# control.net
KiCad netlist of a schematic drawn in EAGLE
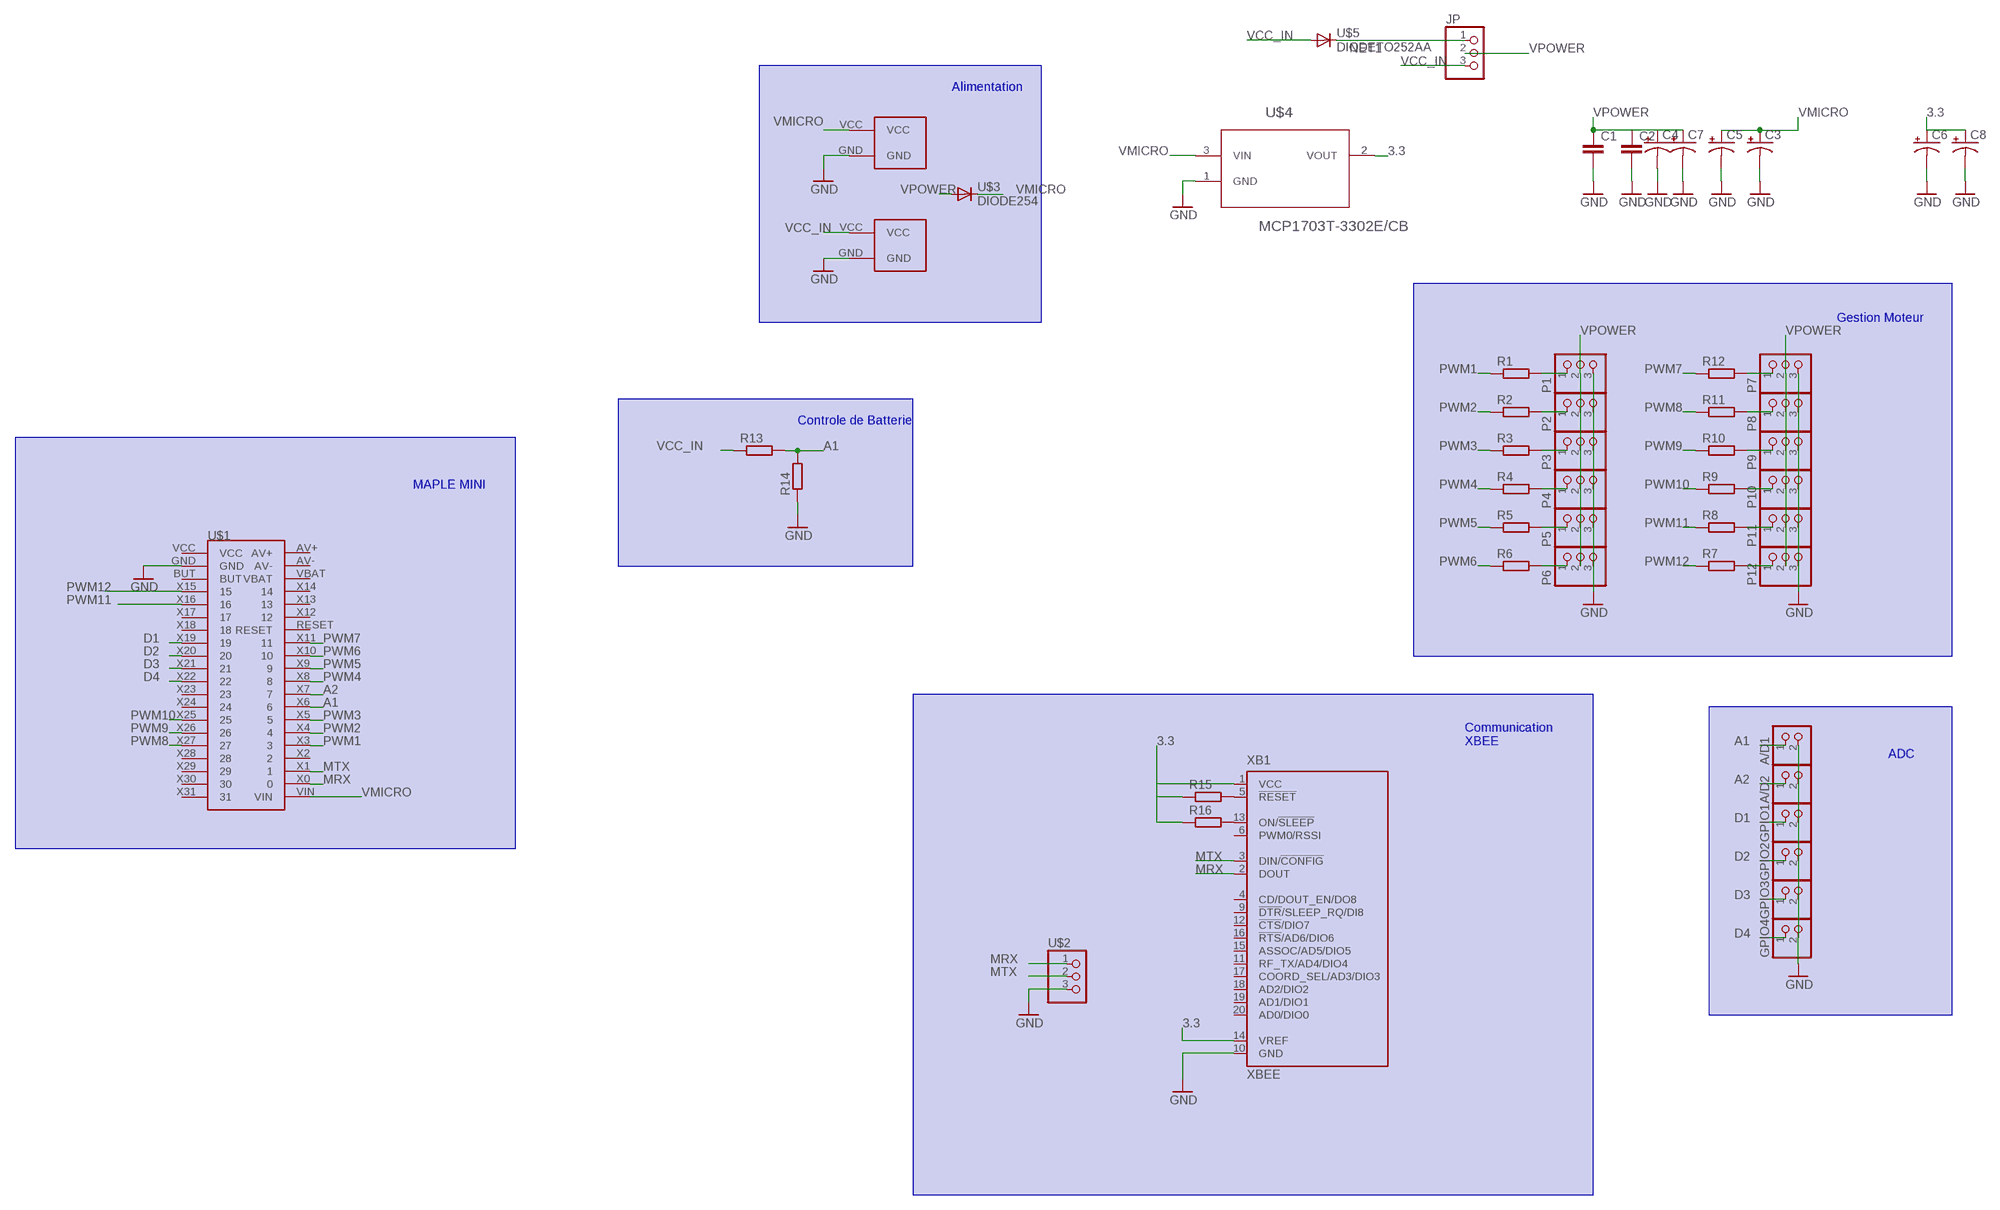
[diagram p0: schematic, sheet 1]

(export (version "E")
  (design (tool "Eeschema 10.0.6"))
  (components
    (comp (ref "A/D1")
      (value "CONNEC_1X02")
      (footprint "eagle-import:CONNEC_1X02")
      (libsource (lib "eagle-import") (part "CONNEC_1X02"))
    )
    (comp (ref "A/D2")
      (value "CONNEC_1X02")
      (footprint "eagle-import:CONNEC_1X02")
      (libsource (lib "eagle-import") (part "CONNEC_1X02"))
    )
    (comp (ref "C1")
      (value "C-EU075-032X103")
      (footprint "eagle-import:C075-032X103")
      (libsource (lib "eagle-import") (part "C-EU075-032X103"))
    )
    (comp (ref "C2")
      (value "C-EU075-032X103")
      (footprint "eagle-import:C075-032X103")
      (libsource (lib "eagle-import") (part "C-EU075-032X103"))
    )
    (comp (ref "C3")
      (value "CAP_POLPTH2")
      (footprint "eagle-import:CPOL-RADIAL-10UF-25V")
      (libsource (lib "eagle-import") (part "CAP_POLPTH2"))
    )
    (comp (ref "C4")
      (value "CAP_POLPTH2")
      (footprint "eagle-import:CPOL-RADIAL-10UF-25V")
      (libsource (lib "eagle-import") (part "CAP_POLPTH2"))
    )
    (comp (ref "C5")
      (value "CAP_POLPTH2")
      (footprint "eagle-import:CPOL-RADIAL-10UF-25V")
      (libsource (lib "eagle-import") (part "CAP_POLPTH2"))
    )
    (comp (ref "C6")
      (value "CAP_POLPTH2")
      (footprint "eagle-import:CPOL-RADIAL-10UF-25V")
      (libsource (lib "eagle-import") (part "CAP_POLPTH2"))
    )
    (comp (ref "C7")
      (value "CAP_POLPTH2")
      (footprint "eagle-import:CPOL-RADIAL-10UF-25V")
      (libsource (lib "eagle-import") (part "CAP_POLPTH2"))
    )
    (comp (ref "C8")
      (value "CAP_POLPTH2")
      (footprint "eagle-import:CPOL-RADIAL-10UF-25V")
      (libsource (lib "eagle-import") (part "CAP_POLPTH2"))
    )
    (comp (ref "GPIO1")
      (value "CONNEC_1X02")
      (footprint "eagle-import:CONNEC_1X02")
      (libsource (lib "eagle-import") (part "CONNEC_1X02"))
    )
    (comp (ref "GPIO2")
      (value "CONNEC_1X02")
      (footprint "eagle-import:CONNEC_1X02")
      (libsource (lib "eagle-import") (part "CONNEC_1X02"))
    )
    (comp (ref "GPIO3")
      (value "CONNEC_1X02")
      (footprint "eagle-import:CONNEC_1X02")
      (libsource (lib "eagle-import") (part "CONNEC_1X02"))
    )
    (comp (ref "GPIO4")
      (value "CONNEC_1X02")
      (footprint "eagle-import:CONNEC_1X02")
      (libsource (lib "eagle-import") (part "CONNEC_1X02"))
    )
    (comp (ref "JP")
      (value "CONNEC_1X03")
      (footprint "eagle-import:CONNEC_1X03")
      (libsource (lib "eagle-import") (part "CONNEC_1X03"))
    )
    (comp (ref "P1")
      (value "CONNEC_1X03")
      (footprint "eagle-import:CONNEC_1X03")
      (libsource (lib "eagle-import") (part "rhoban_CONNEC_1X03"))
    )
    (comp (ref "P2")
      (value "CONNEC_1X03")
      (footprint "eagle-import:CONNEC_1X03")
      (libsource (lib "eagle-import") (part "rhoban_CONNEC_1X03"))
    )
    (comp (ref "P3")
      (value "CONNEC_1X03")
      (footprint "eagle-import:CONNEC_1X03")
      (libsource (lib "eagle-import") (part "rhoban_CONNEC_1X03"))
    )
    (comp (ref "P4")
      (value "CONNEC_1X03")
      (footprint "eagle-import:CONNEC_1X03")
      (libsource (lib "eagle-import") (part "rhoban_CONNEC_1X03"))
    )
    (comp (ref "P5")
      (value "CONNEC_1X03")
      (footprint "eagle-import:CONNEC_1X03")
      (libsource (lib "eagle-import") (part "rhoban_CONNEC_1X03"))
    )
    (comp (ref "P6")
      (value "CONNEC_1X03")
      (footprint "eagle-import:CONNEC_1X03")
      (libsource (lib "eagle-import") (part "rhoban_CONNEC_1X03"))
    )
    (comp (ref "P7")
      (value "CONNEC_1X03")
      (footprint "eagle-import:CONNEC_1X03")
      (libsource (lib "eagle-import") (part "rhoban_CONNEC_1X03"))
    )
    (comp (ref "P8")
      (value "CONNEC_1X03")
      (footprint "eagle-import:CONNEC_1X03")
      (libsource (lib "eagle-import") (part "rhoban_CONNEC_1X03"))
    )
    (comp (ref "P9")
      (value "CONNEC_1X03")
      (footprint "eagle-import:CONNEC_1X03")
      (libsource (lib "eagle-import") (part "rhoban_CONNEC_1X03"))
    )
    (comp (ref "P10")
      (value "CONNEC_1X03")
      (footprint "eagle-import:CONNEC_1X03")
      (libsource (lib "eagle-import") (part "rhoban_CONNEC_1X03"))
    )
    (comp (ref "P11")
      (value "CONNEC_1X03")
      (footprint "eagle-import:CONNEC_1X03")
      (libsource (lib "eagle-import") (part "rhoban_CONNEC_1X03"))
    )
    (comp (ref "P12")
      (value "CONNEC_1X03")
      (footprint "eagle-import:CONNEC_1X03")
      (libsource (lib "eagle-import") (part "rhoban_CONNEC_1X03"))
    )
    (comp (ref "R1")
      (value "RESISTANCE-R0805")
      (footprint "eagle-import:R0805")
      (libsource (lib "eagle-import") (part "RESISTANCE-R0805"))
    )
    (comp (ref "R2")
      (value "RESISTANCE-R0805")
      (footprint "eagle-import:R0805")
      (libsource (lib "eagle-import") (part "RESISTANCE-R0805"))
    )
    (comp (ref "R3")
      (value "RESISTANCE-R0805")
      (footprint "eagle-import:R0805")
      (libsource (lib "eagle-import") (part "RESISTANCE-R0805"))
    )
    (comp (ref "R4")
      (value "RESISTANCE-R0805")
      (footprint "eagle-import:R0805")
      (libsource (lib "eagle-import") (part "RESISTANCE-R0805"))
    )
    (comp (ref "R5")
      (value "RESISTANCE-R0805")
      (footprint "eagle-import:R0805")
      (libsource (lib "eagle-import") (part "RESISTANCE-R0805"))
    )
    (comp (ref "R6")
      (value "RESISTANCE-R0805")
      (footprint "eagle-import:R0805")
      (libsource (lib "eagle-import") (part "RESISTANCE-R0805"))
    )
    (comp (ref "R7")
      (value "RESISTANCE-R0805")
      (footprint "eagle-import:R0805")
      (libsource (lib "eagle-import") (part "RESISTANCE-R0805"))
    )
    (comp (ref "R8")
      (value "RESISTANCE-R0805")
      (footprint "eagle-import:R0805")
      (libsource (lib "eagle-import") (part "RESISTANCE-R0805"))
    )
    (comp (ref "R9")
      (value "RESISTANCE-R0805")
      (footprint "eagle-import:R0805")
      (libsource (lib "eagle-import") (part "RESISTANCE-R0805"))
    )
    (comp (ref "R10")
      (value "RESISTANCE-R0805")
      (footprint "eagle-import:R0805")
      (libsource (lib "eagle-import") (part "RESISTANCE-R0805"))
    )
    (comp (ref "R11")
      (value "RESISTANCE-R0805")
      (footprint "eagle-import:R0805")
      (libsource (lib "eagle-import") (part "RESISTANCE-R0805"))
    )
    (comp (ref "R12")
      (value "RESISTANCE-R0805")
      (footprint "eagle-import:R0805")
      (libsource (lib "eagle-import") (part "RESISTANCE-R0805"))
    )
    (comp (ref "R13")
      (value "R-EU_R0805")
      (footprint "eagle-import:R0805")
      (libsource (lib "eagle-import") (part "R-EU_R0805"))
    )
    (comp (ref "R14")
      (value "R-EU_R0805")
      (footprint "eagle-import:R0805")
      (libsource (lib "eagle-import") (part "R-EU_R0805"))
    )
    (comp (ref "R15")
      (value "R-EU_R0805")
      (footprint "eagle-import:R0805")
      (libsource (lib "eagle-import") (part "R-EU_R0805"))
    )
    (comp (ref "R16")
      (value "R-EU_R0805")
      (footprint "eagle-import:R0805")
      (libsource (lib "eagle-import") (part "R-EU_R0805"))
    )
    (comp (ref "U$1")
      (value "MAPLE_MINI")
      (footprint "eagle-import:CONNEC_2X20")
      (libsource (lib "eagle-import") (part "MAPLE_MINI"))
    )
    (comp (ref "U$2")
      (value "CONNEC_1X03")
      (footprint "eagle-import:CONNEC_1X03")
      (libsource (lib "eagle-import") (part "CONNEC_1X03"))
    )
    (comp (ref "U$3")
      (value "DIODE254")
      (footprint "eagle-import:DIODE_254")
      (libsource (lib "eagle-import") (part "RobotCampus_DIODE254"))
    )
    (comp (ref "U$4")
      (value "MCP1703T-3302E/CB")
      (footprint "eagle-import:SOT95P300X145-3N")
      (libsource (lib "eagle-import") (part "MCP1703T-3302E/CB"))
    )
    (comp (ref "U$5")
      (value "DIODETO252AA")
      (footprint "eagle-import:TO-252AA")
      (libsource (lib "eagle-import") (part "DIODETO252AA"))
    )
    (comp (ref "U$10")
      (value "JST_2")
      (footprint "eagle-import:JST_2")
      (libsource (lib "eagle-import") (part "JST_2"))
    )
    (comp (ref "U$11")
      (value "JST_2")
      (footprint "eagle-import:JST_2")
      (libsource (lib "eagle-import") (part "JST_2"))
    )
    (comp (ref "XB1")
      (value "XBEE")
      (footprint "eagle-import:XBEE")
      (fields (field (name "MPN") "XBP24-Z7UIT-004"))
      (libsource (lib "eagle-import") (part "XBEE"))
    )
  )
  (nets
    (net (code "1") (name "/3.3") (class "Default")
      (node (ref "C6") (pin "1") (pinfunction "+_1") (pintype "passive"))
      (node (ref "C8") (pin "1") (pinfunction "+_1") (pintype "passive"))
      (node (ref "R15") (pin "1") (pinfunction "1_1") (pintype "passive"))
      (node (ref "R16") (pin "1") (pinfunction "1_1") (pintype "passive"))
      (node (ref "U$4") (pin "2") (pinfunction "VOUT_2") (pintype "output"))
      (node (ref "XB1") (pin "1") (pinfunction "VCC_1") (pintype "power_in"))
      (node (ref "XB1") (pin "14") (pinfunction "VREF_14") (pintype "input"))
    )
    (net (code "2") (name "/A1") (class "Default")
      (node (ref "A/D1") (pin "1") (pinfunction "1_1") (pintype "passive"))
      (node (ref "R13") (pin "2") (pinfunction "2_2") (pintype "passive"))
      (node (ref "R14") (pin "2") (pinfunction "2_2") (pintype "passive"))
      (node (ref "U$1") (pin "X6") (pinfunction "6_X6") (pintype "bidirectional"))
    )
    (net (code "3") (name "/A2") (class "Default")
      (node (ref "A/D2") (pin "1") (pinfunction "1_1") (pintype "passive"))
      (node (ref "U$1") (pin "X7") (pinfunction "7_X7") (pintype "bidirectional"))
    )
    (net (code "4") (name "/D1") (class "Default")
      (node (ref "GPIO1") (pin "1") (pinfunction "1_1") (pintype "passive"))
      (node (ref "U$1") (pin "X19") (pinfunction "19_X19") (pintype "bidirectional"))
    )
    (net (code "5") (name "/D2") (class "Default")
      (node (ref "GPIO2") (pin "1") (pinfunction "1_1") (pintype "passive"))
      (node (ref "U$1") (pin "X20") (pinfunction "20_X20") (pintype "bidirectional"))
    )
    (net (code "6") (name "/D3") (class "Default")
      (node (ref "GPIO3") (pin "1") (pinfunction "1_1") (pintype "passive"))
      (node (ref "U$1") (pin "X21") (pinfunction "21_X21") (pintype "bidirectional"))
    )
    (net (code "7") (name "/D4") (class "Default")
      (node (ref "GPIO4") (pin "1") (pinfunction "1_1") (pintype "passive"))
      (node (ref "U$1") (pin "X22") (pinfunction "22_X22") (pintype "bidirectional"))
    )
    (net (code "8") (name "/MRX") (class "Default")
      (node (ref "U$1") (pin "X0") (pinfunction "0_X0") (pintype "bidirectional"))
      (node (ref "U$2") (pin "1") (pinfunction "1_1") (pintype "passive"))
      (node (ref "XB1") (pin "2") (pinfunction "DOUT_2") (pintype "output"))
    )
    (net (code "9") (name "/MTX") (class "Default")
      (node (ref "U$1") (pin "X1") (pinfunction "1_X1") (pintype "bidirectional"))
      (node (ref "U$2") (pin "2") (pinfunction "2_2") (pintype "passive"))
      (node (ref "XB1") (pin "3") (pinfunction "DIN/~{CONFIG}_3") (pintype "input"))
    )
    (net (code "10") (name "/NET1") (class "Default")
      (node (ref "JP") (pin "1") (pinfunction "1_1") (pintype "passive"))
      (node (ref "U$5") (pin "4") (pinfunction "C_4") (pintype "passive"))
    )
    (net (code "11") (name "/PWM1") (class "Default")
      (node (ref "R1") (pin "1") (pinfunction "1_1") (pintype "passive"))
      (node (ref "U$1") (pin "X3") (pinfunction "3_X3") (pintype "bidirectional"))
    )
    (net (code "12") (name "/PWM2") (class "Default")
      (node (ref "R2") (pin "1") (pinfunction "1_1") (pintype "passive"))
      (node (ref "U$1") (pin "X4") (pinfunction "4_X4") (pintype "bidirectional"))
    )
    (net (code "13") (name "/PWM3") (class "Default")
      (node (ref "R3") (pin "1") (pinfunction "1_1") (pintype "passive"))
      (node (ref "U$1") (pin "X5") (pinfunction "5_X5") (pintype "bidirectional"))
    )
    (net (code "14") (name "/PWM4") (class "Default")
      (node (ref "R4") (pin "1") (pinfunction "1_1") (pintype "passive"))
      (node (ref "U$1") (pin "X8") (pinfunction "8_X8") (pintype "bidirectional"))
    )
    (net (code "15") (name "/PWM5") (class "Default")
      (node (ref "R5") (pin "1") (pinfunction "1_1") (pintype "passive"))
      (node (ref "U$1") (pin "X9") (pinfunction "9_X9") (pintype "bidirectional"))
    )
    (net (code "16") (name "/PWM6") (class "Default")
      (node (ref "R6") (pin "1") (pinfunction "1_1") (pintype "passive"))
      (node (ref "U$1") (pin "X10") (pinfunction "10_X10") (pintype "bidirectional"))
    )
    (net (code "17") (name "/PWM7") (class "Default")
      (node (ref "R12") (pin "1") (pinfunction "1_1") (pintype "passive"))
      (node (ref "U$1") (pin "X11") (pinfunction "11_X11") (pintype "bidirectional"))
    )
    (net (code "18") (name "/PWM8") (class "Default")
      (node (ref "R11") (pin "1") (pinfunction "1_1") (pintype "passive"))
      (node (ref "U$1") (pin "X27") (pinfunction "27_X27") (pintype "bidirectional"))
    )
    (net (code "19") (name "/PWM9") (class "Default")
      (node (ref "R10") (pin "1") (pinfunction "1_1") (pintype "passive"))
      (node (ref "U$1") (pin "X26") (pinfunction "26_X26") (pintype "bidirectional"))
    )
    (net (code "20") (name "/PWM10") (class "Default")
      (node (ref "R9") (pin "1") (pinfunction "1_1") (pintype "passive"))
      (node (ref "U$1") (pin "X25") (pinfunction "25_X25") (pintype "bidirectional"))
    )
    (net (code "21") (name "/PWM11") (class "Default")
      (node (ref "R8") (pin "1") (pinfunction "1_1") (pintype "passive"))
      (node (ref "U$1") (pin "X16") (pinfunction "16_X16") (pintype "bidirectional"))
    )
    (net (code "22") (name "/PWM12") (class "Default")
      (node (ref "R7") (pin "1") (pinfunction "1_1") (pintype "passive"))
      (node (ref "U$1") (pin "X15") (pinfunction "15_X15") (pintype "bidirectional"))
    )
    (net (code "23") (name "/VCC_IN") (class "Default")
      (node (ref "JP") (pin "3") (pinfunction "3_3") (pintype "passive"))
      (node (ref "R13") (pin "1") (pinfunction "1_1") (pintype "passive"))
      (node (ref "U$11") (pin "VCC") (pinfunction "VCC_VCC") (pintype "bidirectional"))
      (node (ref "U$5") (pin "3") (pinfunction "A_3") (pintype "passive"))
    )
    (net (code "24") (name "/VMICRO") (class "Default")
      (node (ref "C3") (pin "1") (pinfunction "+_1") (pintype "passive"))
      (node (ref "C5") (pin "1") (pinfunction "+_1") (pintype "passive"))
      (node (ref "U$1") (pin "VIN") (pinfunction "VIN_VIN") (pintype "bidirectional"))
      (node (ref "U$10") (pin "VCC") (pinfunction "VCC_VCC") (pintype "bidirectional"))
      (node (ref "U$3") (pin "B") (pinfunction "C_B") (pintype "passive"))
      (node (ref "U$4") (pin "3") (pinfunction "VIN_3") (pintype "input"))
    )
    (net (code "25") (name "/VPOWER") (class "Default")
      (node (ref "C1") (pin "1") (pinfunction "1_1") (pintype "passive"))
      (node (ref "C2") (pin "1") (pinfunction "1_1") (pintype "passive"))
      (node (ref "C4") (pin "1") (pinfunction "+_1") (pintype "passive"))
      (node (ref "C7") (pin "1") (pinfunction "+_1") (pintype "passive"))
      (node (ref "JP") (pin "2") (pinfunction "2_2") (pintype "passive"))
      (node (ref "P1") (pin "2") (pinfunction "2_2") (pintype "passive"))
      (node (ref "P10") (pin "2") (pinfunction "2_2") (pintype "passive"))
      (node (ref "P11") (pin "2") (pinfunction "2_2") (pintype "passive"))
      (node (ref "P12") (pin "2") (pinfunction "2_2") (pintype "passive"))
      (node (ref "P2") (pin "2") (pinfunction "2_2") (pintype "passive"))
      (node (ref "P3") (pin "2") (pinfunction "2_2") (pintype "passive"))
      (node (ref "P4") (pin "2") (pinfunction "2_2") (pintype "passive"))
      (node (ref "P5") (pin "2") (pinfunction "2_2") (pintype "passive"))
      (node (ref "P6") (pin "2") (pinfunction "2_2") (pintype "passive"))
      (node (ref "P7") (pin "2") (pinfunction "2_2") (pintype "passive"))
      (node (ref "P8") (pin "2") (pinfunction "2_2") (pintype "passive"))
      (node (ref "P9") (pin "2") (pinfunction "2_2") (pintype "passive"))
      (node (ref "U$3") (pin "A") (pinfunction "A_A") (pintype "passive"))
    )
    (net (code "26") (name "GND") (class "Default")
      (node (ref "A/D1") (pin "2") (pinfunction "2_2") (pintype "passive"))
      (node (ref "A/D2") (pin "2") (pinfunction "2_2") (pintype "passive"))
      (node (ref "C1") (pin "2") (pinfunction "2_2") (pintype "passive"))
      (node (ref "C2") (pin "2") (pinfunction "2_2") (pintype "passive"))
      (node (ref "C3") (pin "2") (pinfunction "-_2") (pintype "passive"))
      (node (ref "C4") (pin "2") (pinfunction "-_2") (pintype "passive"))
      (node (ref "C5") (pin "2") (pinfunction "-_2") (pintype "passive"))
      (node (ref "C6") (pin "2") (pinfunction "-_2") (pintype "passive"))
      (node (ref "C7") (pin "2") (pinfunction "-_2") (pintype "passive"))
      (node (ref "C8") (pin "2") (pinfunction "-_2") (pintype "passive"))
      (node (ref "GPIO1") (pin "2") (pinfunction "2_2") (pintype "passive"))
      (node (ref "GPIO2") (pin "2") (pinfunction "2_2") (pintype "passive"))
      (node (ref "GPIO3") (pin "2") (pinfunction "2_2") (pintype "passive"))
      (node (ref "GPIO4") (pin "2") (pinfunction "2_2") (pintype "passive"))
      (node (ref "P1") (pin "3") (pinfunction "3_3") (pintype "passive"))
      (node (ref "P10") (pin "3") (pinfunction "3_3") (pintype "passive"))
      (node (ref "P11") (pin "3") (pinfunction "3_3") (pintype "passive"))
      (node (ref "P12") (pin "3") (pinfunction "3_3") (pintype "passive"))
      (node (ref "P2") (pin "3") (pinfunction "3_3") (pintype "passive"))
      (node (ref "P3") (pin "3") (pinfunction "3_3") (pintype "passive"))
      (node (ref "P4") (pin "3") (pinfunction "3_3") (pintype "passive"))
      (node (ref "P5") (pin "3") (pinfunction "3_3") (pintype "passive"))
      (node (ref "P6") (pin "3") (pinfunction "3_3") (pintype "passive"))
      (node (ref "P7") (pin "3") (pinfunction "3_3") (pintype "passive"))
      (node (ref "P8") (pin "3") (pinfunction "3_3") (pintype "passive"))
      (node (ref "P9") (pin "3") (pinfunction "3_3") (pintype "passive"))
      (node (ref "R14") (pin "1") (pinfunction "1_1") (pintype "passive"))
      (node (ref "U$1") (pin "GND") (pinfunction "GND_GND") (pintype "bidirectional"))
      (node (ref "U$10") (pin "GND") (pinfunction "GND_GND") (pintype "bidirectional"))
      (node (ref "U$11") (pin "GND") (pinfunction "GND_GND") (pintype "bidirectional"))
      (node (ref "U$2") (pin "3") (pinfunction "3_3") (pintype "passive"))
      (node (ref "U$4") (pin "1") (pinfunction "GND_1") (pintype "passive"))
      (node (ref "XB1") (pin "10") (pinfunction "GND_10") (pintype "power_in"))
    )
    (net (code "27") (name "Net-(P1-Pad1)") (class "Default")
      (node (ref "P1") (pin "1") (pinfunction "1_1") (pintype "passive"))
      (node (ref "R1") (pin "2") (pinfunction "2_2") (pintype "passive"))
    )
    (net (code "28") (name "Net-(P2-Pad1)") (class "Default")
      (node (ref "P2") (pin "1") (pinfunction "1_1") (pintype "passive"))
      (node (ref "R2") (pin "2") (pinfunction "2_2") (pintype "passive"))
    )
    (net (code "29") (name "Net-(P3-Pad1)") (class "Default")
      (node (ref "P3") (pin "1") (pinfunction "1_1") (pintype "passive"))
      (node (ref "R3") (pin "2") (pinfunction "2_2") (pintype "passive"))
    )
    (net (code "30") (name "Net-(P4-Pad1)") (class "Default")
      (node (ref "P4") (pin "1") (pinfunction "1_1") (pintype "passive"))
      (node (ref "R4") (pin "2") (pinfunction "2_2") (pintype "passive"))
    )
    (net (code "31") (name "Net-(P5-Pad1)") (class "Default")
      (node (ref "P5") (pin "1") (pinfunction "1_1") (pintype "passive"))
      (node (ref "R5") (pin "2") (pinfunction "2_2") (pintype "passive"))
    )
    (net (code "32") (name "Net-(P6-Pad1)") (class "Default")
      (node (ref "P6") (pin "1") (pinfunction "1_1") (pintype "passive"))
      (node (ref "R6") (pin "2") (pinfunction "2_2") (pintype "passive"))
    )
    (net (code "33") (name "Net-(P7-Pad1)") (class "Default")
      (node (ref "P7") (pin "1") (pinfunction "1_1") (pintype "passive"))
      (node (ref "R12") (pin "2") (pinfunction "2_2") (pintype "passive"))
    )
    (net (code "34") (name "Net-(P8-Pad1)") (class "Default")
      (node (ref "P8") (pin "1") (pinfunction "1_1") (pintype "passive"))
      (node (ref "R11") (pin "2") (pinfunction "2_2") (pintype "passive"))
    )
    (net (code "35") (name "Net-(P9-Pad1)") (class "Default")
      (node (ref "P9") (pin "1") (pinfunction "1_1") (pintype "passive"))
      (node (ref "R10") (pin "2") (pinfunction "2_2") (pintype "passive"))
    )
    (net (code "36") (name "Net-(P10-Pad1)") (class "Default")
      (node (ref "P10") (pin "1") (pinfunction "1_1") (pintype "passive"))
      (node (ref "R9") (pin "2") (pinfunction "2_2") (pintype "passive"))
    )
    (net (code "37") (name "Net-(P11-Pad1)") (class "Default")
      (node (ref "P11") (pin "1") (pinfunction "1_1") (pintype "passive"))
      (node (ref "R8") (pin "2") (pinfunction "2_2") (pintype "passive"))
    )
    (net (code "38") (name "Net-(P12-Pad1)") (class "Default")
      (node (ref "P12") (pin "1") (pinfunction "1_1") (pintype "passive"))
      (node (ref "R7") (pin "2") (pinfunction "2_2") (pintype "passive"))
    )
    (net (code "39") (name "Net-(XB1-ON{slash}~{SLEEP})") (class "Default")
      (node (ref "R16") (pin "2") (pinfunction "2_2") (pintype "passive"))
      (node (ref "XB1") (pin "13") (pinfunction "ON/~{SLEEP}_13") (pintype "output"))
    )
    (net (code "40") (name "Net-(XB1-~{RESET})") (class "Default")
      (node (ref "R15") (pin "2") (pinfunction "2_2") (pintype "passive"))
      (node (ref "XB1") (pin "5") (pinfunction "~{RESET}_5") (pintype "input"))
    )
    (net (code "41") (name "unconnected-(U$1-2-PadX2)") (class "Default")
      (node (ref "U$1") (pin "X2") (pinfunction "2_X2") (pintype "bidirectional"))
    )
    (net (code "42") (name "unconnected-(U$1-12-PadX12)") (class "Default")
      (node (ref "U$1") (pin "X12") (pinfunction "12_X12") (pintype "bidirectional"))
    )
    (net (code "43") (name "unconnected-(U$1-13-PadX13)") (class "Default")
      (node (ref "U$1") (pin "X13") (pinfunction "13_X13") (pintype "bidirectional"))
    )
    (net (code "44") (name "unconnected-(U$1-14-PadX14)") (class "Default")
      (node (ref "U$1") (pin "X14") (pinfunction "14_X14") (pintype "bidirectional"))
    )
    (net (code "45") (name "unconnected-(U$1-17-PadX17)") (class "Default")
      (node (ref "U$1") (pin "X17") (pinfunction "17_X17") (pintype "bidirectional"))
    )
    (net (code "46") (name "unconnected-(U$1-18-PadX18)") (class "Default")
      (node (ref "U$1") (pin "X18") (pinfunction "18_X18") (pintype "bidirectional"))
    )
    (net (code "47") (name "unconnected-(U$1-23-PadX23)") (class "Default")
      (node (ref "U$1") (pin "X23") (pinfunction "23_X23") (pintype "bidirectional"))
    )
    (net (code "48") (name "unconnected-(U$1-24-PadX24)") (class "Default")
      (node (ref "U$1") (pin "X24") (pinfunction "24_X24") (pintype "bidirectional"))
    )
    (net (code "49") (name "unconnected-(U$1-28-PadX28)") (class "Default")
      (node (ref "U$1") (pin "X28") (pinfunction "28_X28") (pintype "bidirectional"))
    )
    (net (code "50") (name "unconnected-(U$1-29-PadX29)") (class "Default")
      (node (ref "U$1") (pin "X29") (pinfunction "29_X29") (pintype "bidirectional"))
    )
    (net (code "51") (name "unconnected-(U$1-30-PadX30)") (class "Default")
      (node (ref "U$1") (pin "X30") (pinfunction "30_X30") (pintype "bidirectional"))
    )
    (net (code "52") (name "unconnected-(U$1-31-PadX31)") (class "Default")
      (node (ref "U$1") (pin "X31") (pinfunction "31_X31") (pintype "bidirectional"))
    )
    (net (code "53") (name "unconnected-(U$1-PadAV+)") (class "Default")
      (node (ref "U$1") (pin "AV+") (pinfunction "AV+_AV+") (pintype "bidirectional"))
    )
    (net (code "54") (name "unconnected-(U$1-PadAV-)") (class "Default")
      (node (ref "U$1") (pin "AV-") (pinfunction "AV-_AV-") (pintype "bidirectional"))
    )
    (net (code "55") (name "unconnected-(U$1-PadBUT)") (class "Default")
      (node (ref "U$1") (pin "BUT") (pinfunction "BUT_BUT") (pintype "bidirectional"))
    )
    (net (code "56") (name "unconnected-(U$1-PadRESET)") (class "Default")
      (node (ref "U$1") (pin "RESET") (pinfunction "RESET_RESET") (pintype "bidirectional"))
    )
    (net (code "57") (name "unconnected-(U$1-PadVBAT)") (class "Default")
      (node (ref "U$1") (pin "VBAT") (pinfunction "VBAT_VBAT") (pintype "bidirectional"))
    )
    (net (code "58") (name "unconnected-(U$1-PadVCC)") (class "Default")
      (node (ref "U$1") (pin "VCC") (pinfunction "VCC_VCC") (pintype "bidirectional"))
    )
    (net (code "59") (name "unconnected-(XB1-AD0{slash}DIO0-Pad20)") (class "Default")
      (node (ref "XB1") (pin "20") (pinfunction "AD0/DIO0_20") (pintype "bidirectional"))
    )
    (net (code "60") (name "unconnected-(XB1-AD1{slash}DIO1-Pad19)") (class "Default")
      (node (ref "XB1") (pin "19") (pinfunction "AD1/DIO1_19") (pintype "bidirectional"))
    )
    (net (code "61") (name "unconnected-(XB1-AD2{slash}DIO2-Pad18)") (class "Default")
      (node (ref "XB1") (pin "18") (pinfunction "AD2/DIO2_18") (pintype "bidirectional"))
    )
    (net (code "62") (name "unconnected-(XB1-ASSOC{slash}AD5{slash}DIO5-Pad15)") (class "Default")
      (node (ref "XB1") (pin "15") (pinfunction "ASSOC/AD5/DIO5_15") (pintype "bidirectional"))
    )
    (net (code "63") (name "unconnected-(XB1-CD{slash}DOUT_EN{slash}DO8-Pad4)") (class "Default")
      (node (ref "XB1") (pin "4") (pinfunction "CD/DOUT_EN/DO8_4") (pintype "output"))
    )
    (net (code "64") (name "unconnected-(XB1-COORD_SEL{slash}AD3{slash}DIO3-Pad17)") (class "Default")
      (node (ref "XB1") (pin "17") (pinfunction "COORD_SEL/AD3/DIO3_17") (pintype "bidirectional"))
    )
    (net (code "65") (name "unconnected-(XB1-PWM0{slash}RSSI-Pad6)") (class "Default")
      (node (ref "XB1") (pin "6") (pinfunction "PWM0/RSSI_6") (pintype "output"))
    )
    (net (code "66") (name "unconnected-(XB1-RF_TX{slash}AD4{slash}DIO4-Pad11)") (class "Default")
      (node (ref "XB1") (pin "11") (pinfunction "RF_TX/AD4/DIO4_11") (pintype "bidirectional"))
    )
    (net (code "67") (name "unconnected-(XB1-~{CTS}{slash}DIO7-Pad12)") (class "Default")
      (node (ref "XB1") (pin "12") (pinfunction "~{CTS}/DIO7_12") (pintype "bidirectional"))
    )
    (net (code "68") (name "unconnected-(XB1-~{DTR}{slash}SLEEP_RQ{slash}DI8-Pad9)") (class "Default")
      (node (ref "XB1") (pin "9") (pinfunction "~{DTR}/SLEEP_RQ/DI8_9") (pintype "bidirectional"))
    )
    (net (code "69") (name "unconnected-(XB1-~{RTS}{slash}AD6{slash}DIO6-Pad16)") (class "Default")
      (node (ref "XB1") (pin "16") (pinfunction "~{RTS}/AD6/DIO6_16") (pintype "bidirectional"))
    )
  )
)
